# sonar_DAQ_old.net
KiCad netlist of a schematic drawn in Altium Designer
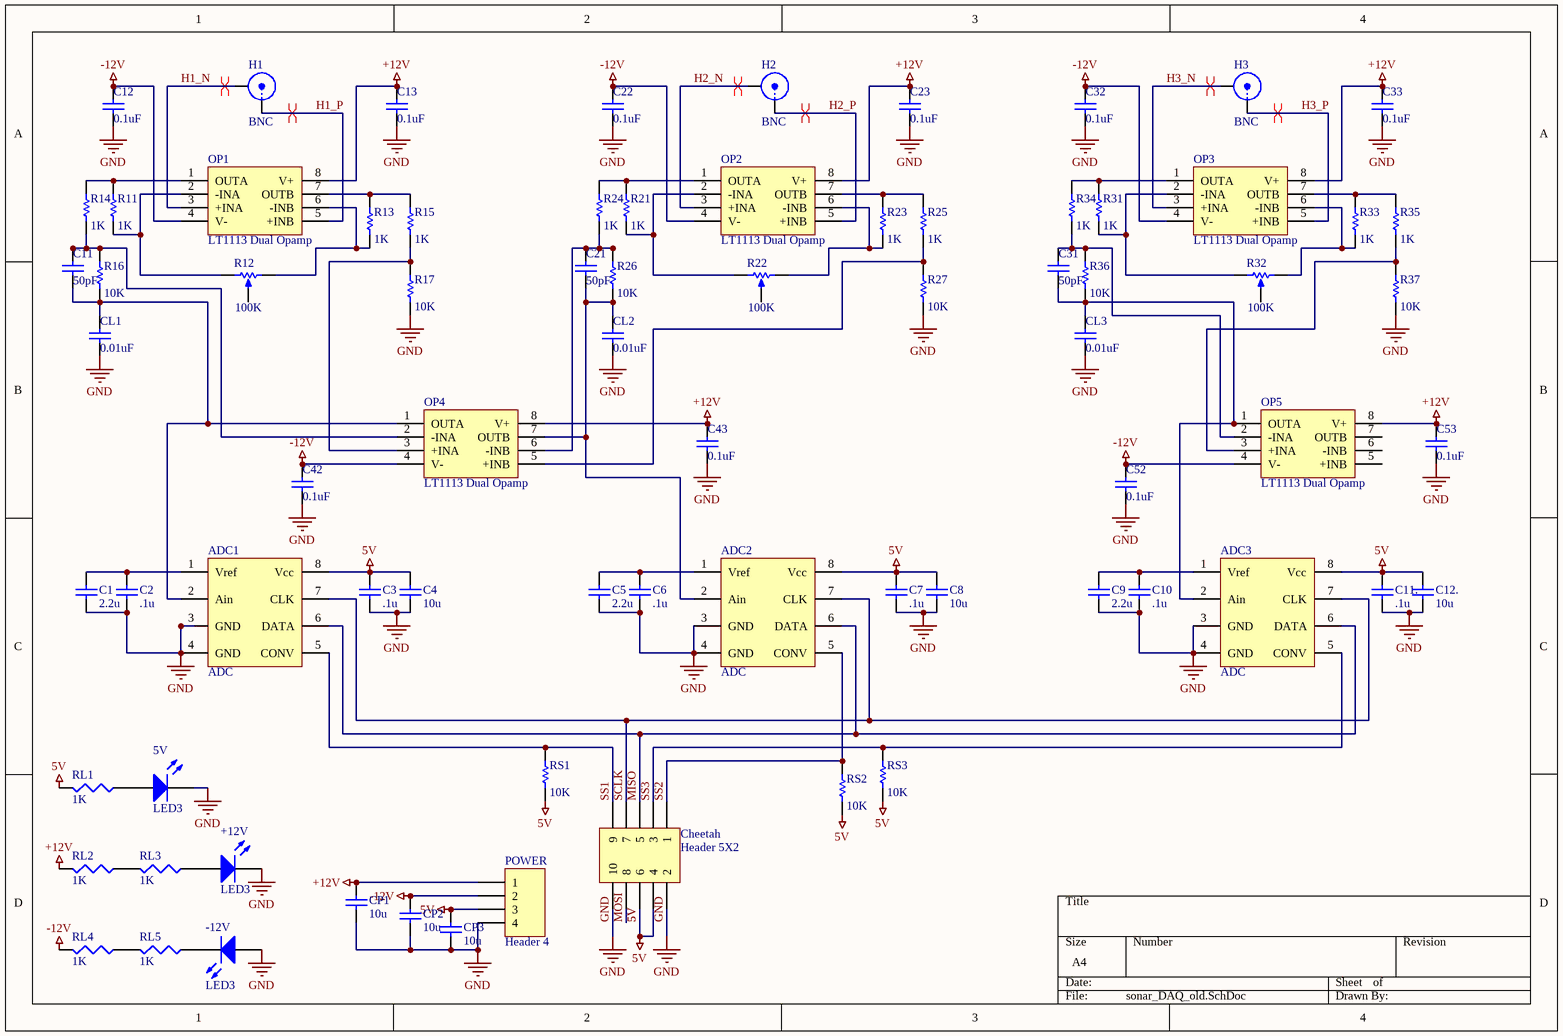
[diagram p0: sonar_DAQ_old.SchDoc]

(export (version "E")
  (design (tool "Eeschema 10.0.6"))
  (components
    (comp (ref "+12V")
      (value "LED3")
      (footprint "0805_led")
      (description "Typical BLUE SiC LED")
      (fields (field (name "PUBLISHER") "Altium Limited"))
      (libsource (lib "Miscellaneous Devices") (part "LED3"))
    )
    (comp (ref "-12V")
      (value "LED3")
      (footprint "0805_led")
      (description "Typical BLUE SiC LED")
      (fields (field (name "PUBLISHER") "Altium Limited"))
      (libsource (lib "Miscellaneous Devices") (part "LED3"))
    )
    (comp (ref "5V")
      (value "LED3")
      (footprint "0805_led")
      (description "Typical BLUE SiC LED")
      (fields (field (name "PUBLISHER") "Altium Limited"))
      (libsource (lib "Miscellaneous Devices") (part "LED3"))
    )
    (comp (ref "ADC1")
      (value "ADC")
      (footprint "ADC")
      (description "ADS7835")
      (libsource (lib "sonar_DAQ") (part "ADC"))
    )
    (comp (ref "ADC2")
      (value "ADC")
      (footprint "ADC")
      (description "ADS7835")
      (libsource (lib "sonar_DAQ") (part "ADC"))
    )
    (comp (ref "ADC3")
      (value "ADC")
      (footprint "ADC")
      (description "ADS7835")
      (libsource (lib "sonar_DAQ") (part "ADC"))
    )
    (comp (ref "C1")
      (value "2.2u")
      (footprint "0805_tantalum_cap")
      (description "Capacitor")
      (fields (field (name "PUBLISHER") "Altium Limited"))
      (libsource (lib "Miscellaneous Devices") (part "Cap"))
    )
    (comp (ref "C2")
      (value ".1u")
      (footprint "0805_ceramic_cap")
      (description "Capacitor")
      (fields (field (name "PUBLISHER") "Altium Limited"))
      (libsource (lib "Miscellaneous Devices") (part "Cap"))
    )
    (comp (ref "C3")
      (value ".1u")
      (footprint "0805_ceramic_cap")
      (description "Capacitor")
      (fields (field (name "PUBLISHER") "Altium Limited"))
      (libsource (lib "Miscellaneous Devices") (part "Cap"))
    )
    (comp (ref "C4")
      (value "10u")
      (footprint "0805_tantalum_cap")
      (description "Capacitor")
      (fields (field (name "PUBLISHER") "Altium Limited"))
      (libsource (lib "Miscellaneous Devices") (part "Cap"))
    )
    (comp (ref "C5")
      (value "2.2u")
      (footprint "0805_tantalum_cap")
      (description "Capacitor")
      (fields (field (name "PUBLISHER") "Altium Limited"))
      (libsource (lib "Miscellaneous Devices") (part "Cap"))
    )
    (comp (ref "C6")
      (value ".1u")
      (footprint "0805_ceramic_cap")
      (description "Capacitor")
      (fields (field (name "PUBLISHER") "Altium Limited"))
      (libsource (lib "Miscellaneous Devices") (part "Cap"))
    )
    (comp (ref "C7")
      (value ".1u")
      (footprint "0805_ceramic_cap")
      (description "Capacitor")
      (fields (field (name "PUBLISHER") "Altium Limited"))
      (libsource (lib "Miscellaneous Devices") (part "Cap"))
    )
    (comp (ref "C8")
      (value "10u")
      (footprint "0805_tantalum_cap")
      (description "Capacitor")
      (fields (field (name "PUBLISHER") "Altium Limited"))
      (libsource (lib "Miscellaneous Devices") (part "Cap"))
    )
    (comp (ref "C9")
      (value "2.2u")
      (footprint "0805_tantalum_cap")
      (description "Capacitor")
      (fields (field (name "PUBLISHER") "Altium Limited"))
      (libsource (lib "Miscellaneous Devices") (part "Cap"))
    )
    (comp (ref "C10")
      (value ".1u")
      (footprint "0805_ceramic_cap")
      (description "Capacitor")
      (fields (field (name "PUBLISHER") "Altium Limited"))
      (libsource (lib "Miscellaneous Devices") (part "Cap"))
    )
    (comp (ref "C11")
      (value "50pF")
      (footprint "0805_ceramic_cap")
      (description "Capacitor")
      (fields (field (name "Comment") "Cap") (field (name "PUBLISHER") "Altium Limited"))
      (libsource (lib "Miscellaneous Devices") (part "Cap"))
    )
    (comp (ref "C11.")
      (value ".1u")
      (footprint "0805_ceramic_cap")
      (description "Capacitor")
      (fields (field (name "PUBLISHER") "Altium Limited"))
      (libsource (lib "Miscellaneous Devices") (part "Cap"))
    )
    (comp (ref "C12")
      (value "0.1uF")
      (footprint "0805_ceramic_cap")
      (description "Capacitor")
      (fields (field (name "Comment") "Cap") (field (name "PUBLISHER") "Altium Limited"))
      (libsource (lib "Miscellaneous Devices") (part "Cap"))
    )
    (comp (ref "C12.")
      (value "10u")
      (footprint "0805_tantalum_cap")
      (description "Capacitor")
      (fields (field (name "PUBLISHER") "Altium Limited"))
      (libsource (lib "Miscellaneous Devices") (part "Cap"))
    )
    (comp (ref "C13")
      (value "0.1uF")
      (footprint "0805_ceramic_cap")
      (description "Capacitor")
      (fields (field (name "Comment") "Cap") (field (name "PUBLISHER") "Altium Limited"))
      (libsource (lib "Miscellaneous Devices") (part "Cap"))
    )
    (comp (ref "C21")
      (value "50pF")
      (footprint "0805_ceramic_cap")
      (description "Capacitor")
      (fields (field (name "Comment") "Cap") (field (name "PUBLISHER") "Altium Limited"))
      (libsource (lib "Miscellaneous Devices") (part "Cap"))
    )
    (comp (ref "C22")
      (value "0.1uF")
      (footprint "0805_ceramic_cap")
      (description "Capacitor")
      (fields (field (name "Comment") "Cap") (field (name "PUBLISHER") "Altium Limited"))
      (libsource (lib "Miscellaneous Devices") (part "Cap"))
    )
    (comp (ref "C23")
      (value "0.1uF")
      (footprint "0805_ceramic_cap")
      (description "Capacitor")
      (fields (field (name "Comment") "Cap") (field (name "PUBLISHER") "Altium Limited"))
      (libsource (lib "Miscellaneous Devices") (part "Cap"))
    )
    (comp (ref "C31")
      (value "50pF")
      (footprint "0805_ceramic_cap")
      (description "Capacitor")
      (fields (field (name "Comment") "Cap") (field (name "PUBLISHER") "Altium Limited"))
      (libsource (lib "Miscellaneous Devices") (part "Cap"))
    )
    (comp (ref "C32")
      (value "0.1uF")
      (footprint "0805_ceramic_cap")
      (description "Capacitor")
      (fields (field (name "Comment") "Cap") (field (name "PUBLISHER") "Altium Limited"))
      (libsource (lib "Miscellaneous Devices") (part "Cap"))
    )
    (comp (ref "C33")
      (value "0.1uF")
      (footprint "0805_ceramic_cap")
      (description "Capacitor")
      (fields (field (name "Comment") "Cap") (field (name "PUBLISHER") "Altium Limited"))
      (libsource (lib "Miscellaneous Devices") (part "Cap"))
    )
    (comp (ref "C42")
      (value "0.1uF")
      (footprint "0805_ceramic_cap")
      (description "Capacitor")
      (fields (field (name "Comment") "Cap") (field (name "PUBLISHER") "Altium Limited"))
      (libsource (lib "Miscellaneous Devices") (part "Cap"))
    )
    (comp (ref "C43")
      (value "0.1uF")
      (footprint "0805_ceramic_cap")
      (description "Capacitor")
      (fields (field (name "Comment") "Cap") (field (name "PUBLISHER") "Altium Limited"))
      (libsource (lib "Miscellaneous Devices") (part "Cap"))
    )
    (comp (ref "C52")
      (value "0.1uF")
      (footprint "0805_ceramic_cap")
      (description "Capacitor")
      (fields (field (name "Comment") "Cap") (field (name "PUBLISHER") "Altium Limited"))
      (libsource (lib "Miscellaneous Devices") (part "Cap"))
    )
    (comp (ref "C53")
      (value "0.1uF")
      (footprint "0805_ceramic_cap")
      (description "Capacitor")
      (fields (field (name "Comment") "Cap") (field (name "PUBLISHER") "Altium Limited"))
      (libsource (lib "Miscellaneous Devices") (part "Cap"))
    )
    (comp (ref "Cheetah")
      (value "Header 5X2")
      (footprint "HDR2X5")
      (description "Header, 5-Pin, Dual row")
      (fields (field (name "PUBLISHER") "Altium Limited"))
      (libsource (lib "Miscellaneous Connectors") (part "Header 5X2"))
    )
    (comp (ref "CL1")
      (value "0.01uF")
      (footprint "0805_ceramic_cap")
      (description "Capacitor")
      (fields (field (name "Comment") "Cap") (field (name "PUBLISHER") "Altium Limited"))
      (libsource (lib "Miscellaneous Devices") (part "Cap"))
    )
    (comp (ref "CL2")
      (value "0.01uF")
      (footprint "0805_ceramic_cap")
      (description "Capacitor")
      (fields (field (name "Comment") "Cap") (field (name "PUBLISHER") "Altium Limited"))
      (libsource (lib "Miscellaneous Devices") (part "Cap"))
    )
    (comp (ref "CL3")
      (value "0.01uF")
      (footprint "0805_ceramic_cap")
      (description "Capacitor")
      (fields (field (name "Comment") "Cap") (field (name "PUBLISHER") "Altium Limited"))
      (libsource (lib "Miscellaneous Devices") (part "Cap"))
    )
    (comp (ref "CP1")
      (value "10u")
      (footprint "0805_tantalum_cap")
      (description "Capacitor")
      (fields (field (name "PUBLISHER") "Altium Limited"))
      (libsource (lib "Miscellaneous Devices") (part "Cap"))
    )
    (comp (ref "CP2")
      (value "10u")
      (footprint "0805_tantalum_cap")
      (description "Capacitor")
      (fields (field (name "PUBLISHER") "Altium Limited"))
      (libsource (lib "Miscellaneous Devices") (part "Cap"))
    )
    (comp (ref "CP3")
      (value "10u")
      (footprint "0805_tantalum_cap")
      (description "Capacitor")
      (fields (field (name "PUBLISHER") "Altium Limited"))
      (libsource (lib "Miscellaneous Devices") (part "Cap"))
    )
    (comp (ref "H1")
      (value "BNC")
      (footprint "BNC")
      (description "BNC Elbow Connector")
      (fields (field (name "PUBLISHER") "Altium Limited"))
      (libsource (lib "Miscellaneous Connectors") (part "BNC"))
    )
    (comp (ref "H2")
      (value "BNC")
      (footprint "BNC")
      (description "BNC Elbow Connector")
      (fields (field (name "PUBLISHER") "Altium Limited"))
      (libsource (lib "Miscellaneous Connectors") (part "BNC"))
    )
    (comp (ref "H3")
      (value "BNC")
      (footprint "BNC")
      (description "BNC Elbow Connector")
      (fields (field (name "PUBLISHER") "Altium Limited"))
      (libsource (lib "Miscellaneous Connectors") (part "BNC"))
    )
    (comp (ref "OP1")
      (value "LT1113 Dual Opamp")
      (footprint "lt1113_opamp")
      (libsource (lib "sonar_DAQ") (part "LT1113 OPAMP"))
    )
    (comp (ref "OP2")
      (value "LT1113 Dual Opamp")
      (footprint "lt1113_opamp")
      (libsource (lib "sonar_DAQ") (part "LT1113 OPAMP"))
    )
    (comp (ref "OP3")
      (value "LT1113 Dual Opamp")
      (footprint "lt1113_opamp")
      (libsource (lib "sonar_DAQ") (part "LT1113 OPAMP"))
    )
    (comp (ref "OP4")
      (value "LT1113 Dual Opamp")
      (footprint "lt1113_opamp")
      (libsource (lib "sonar_DAQ") (part "LT1113 OPAMP"))
    )
    (comp (ref "OP5")
      (value "LT1113 Dual Opamp")
      (footprint "lt1113_opamp")
      (libsource (lib "sonar_DAQ") (part "LT1113 OPAMP"))
    )
    (comp (ref "POWER")
      (value "Header 4")
      (footprint "HDR1X4")
      (description "Header, 4-Pin")
      (fields (field (name "PUBLISHER") "Altium Limited"))
      (libsource (lib "Miscellaneous Connectors") (part "Header 4"))
    )
    (comp (ref "R11")
      (value "1K")
      (footprint "0805_res")
      (description "Resistor")
      (fields (field (name "Comment") "Res1") (field (name "PUBLISHER") "Altium Limited"))
      (libsource (lib "Miscellaneous Devices") (part "Res1"))
    )
    (comp (ref "R12")
      (value "100K")
      (footprint "trimmer_pot")
      (description "Potentiometer")
      (fields (field (name "Comment") "RPot") (field (name "PUBLISHER") "Altium Limited"))
      (libsource (lib "Miscellaneous Devices") (part "RPot"))
    )
    (comp (ref "R13")
      (value "1K")
      (footprint "0805_res")
      (description "Resistor")
      (fields (field (name "Comment") "Res1") (field (name "PUBLISHER") "Altium Limited"))
      (libsource (lib "Miscellaneous Devices") (part "Res1"))
    )
    (comp (ref "R14")
      (value "1K")
      (footprint "0805_res")
      (description "Resistor")
      (fields (field (name "Comment") "Res1") (field (name "PUBLISHER") "Altium Limited"))
      (libsource (lib "Miscellaneous Devices") (part "Res1"))
    )
    (comp (ref "R15")
      (value "1K")
      (footprint "0805_res")
      (description "Resistor")
      (fields (field (name "Comment") "Res1") (field (name "PUBLISHER") "Altium Limited"))
      (libsource (lib "Miscellaneous Devices") (part "Res1"))
    )
    (comp (ref "R16")
      (value "10K")
      (footprint "0805_res")
      (description "Resistor")
      (fields (field (name "Comment") "Res1") (field (name "PUBLISHER") "Altium Limited"))
      (libsource (lib "Miscellaneous Devices") (part "Res1"))
    )
    (comp (ref "R17")
      (value "10K")
      (footprint "0805_res")
      (description "Resistor")
      (fields (field (name "Comment") "Res1") (field (name "PUBLISHER") "Altium Limited"))
      (libsource (lib "Miscellaneous Devices") (part "Res1"))
    )
    (comp (ref "R21")
      (value "1K")
      (footprint "0805_res")
      (description "Resistor")
      (fields (field (name "Comment") "Res1") (field (name "PUBLISHER") "Altium Limited"))
      (libsource (lib "Miscellaneous Devices") (part "Res1"))
    )
    (comp (ref "R22")
      (value "100K")
      (footprint "trimmer_pot")
      (description "Potentiometer")
      (fields (field (name "Comment") "RPot") (field (name "PUBLISHER") "Altium Limited"))
      (libsource (lib "Miscellaneous Devices") (part "RPot"))
    )
    (comp (ref "R23")
      (value "1K")
      (footprint "0805_res")
      (description "Resistor")
      (fields (field (name "Comment") "Res1") (field (name "PUBLISHER") "Altium Limited"))
      (libsource (lib "Miscellaneous Devices") (part "Res1"))
    )
    (comp (ref "R24")
      (value "1K")
      (footprint "0805_res")
      (description "Resistor")
      (fields (field (name "Comment") "Res1") (field (name "PUBLISHER") "Altium Limited"))
      (libsource (lib "Miscellaneous Devices") (part "Res1"))
    )
    (comp (ref "R25")
      (value "1K")
      (footprint "0805_res")
      (description "Resistor")
      (fields (field (name "Comment") "Res1") (field (name "PUBLISHER") "Altium Limited"))
      (libsource (lib "Miscellaneous Devices") (part "Res1"))
    )
    (comp (ref "R26")
      (value "10K")
      (footprint "0805_res")
      (description "Resistor")
      (fields (field (name "Comment") "Res1") (field (name "PUBLISHER") "Altium Limited"))
      (libsource (lib "Miscellaneous Devices") (part "Res1"))
    )
    (comp (ref "R27")
      (value "10K")
      (footprint "0805_res")
      (description "Resistor")
      (fields (field (name "Comment") "Res1") (field (name "PUBLISHER") "Altium Limited"))
      (libsource (lib "Miscellaneous Devices") (part "Res1"))
    )
    (comp (ref "R31")
      (value "1K")
      (footprint "0805_res")
      (description "Resistor")
      (fields (field (name "Comment") "Res1") (field (name "PUBLISHER") "Altium Limited"))
      (libsource (lib "Miscellaneous Devices") (part "Res1"))
    )
    (comp (ref "R32")
      (value "100K")
      (footprint "trimmer_pot")
      (description "Potentiometer")
      (fields (field (name "Comment") "RPot") (field (name "PUBLISHER") "Altium Limited"))
      (libsource (lib "Miscellaneous Devices") (part "RPot"))
    )
    (comp (ref "R33")
      (value "1K")
      (footprint "0805_res")
      (description "Resistor")
      (fields (field (name "Comment") "Res1") (field (name "PUBLISHER") "Altium Limited"))
      (libsource (lib "Miscellaneous Devices") (part "Res1"))
    )
    (comp (ref "R34")
      (value "1K")
      (footprint "0805_res")
      (description "Resistor")
      (fields (field (name "Comment") "Res1") (field (name "PUBLISHER") "Altium Limited"))
      (libsource (lib "Miscellaneous Devices") (part "Res1"))
    )
    (comp (ref "R35")
      (value "1K")
      (footprint "0805_res")
      (description "Resistor")
      (fields (field (name "Comment") "Res1") (field (name "PUBLISHER") "Altium Limited"))
      (libsource (lib "Miscellaneous Devices") (part "Res1"))
    )
    (comp (ref "R36")
      (value "10K")
      (footprint "0805_res")
      (description "Resistor")
      (fields (field (name "Comment") "Res1") (field (name "PUBLISHER") "Altium Limited"))
      (libsource (lib "Miscellaneous Devices") (part "Res1"))
    )
    (comp (ref "R37")
      (value "10K")
      (footprint "0805_res")
      (description "Resistor")
      (fields (field (name "Comment") "Res1") (field (name "PUBLISHER") "Altium Limited"))
      (libsource (lib "Miscellaneous Devices") (part "Res1"))
    )
    (comp (ref "RL1")
      (value "1K")
      (footprint "0805_res")
      (description "Resistor")
      (fields (field (name "Comment") "Res3") (field (name "PUBLISHER") "Altium Limited"))
      (libsource (lib "Miscellaneous Devices") (part "Res3"))
    )
    (comp (ref "RL2")
      (value "1K")
      (footprint "0805_res")
      (description "Resistor")
      (fields (field (name "Comment") "Res3") (field (name "PUBLISHER") "Altium Limited"))
      (libsource (lib "Miscellaneous Devices") (part "Res3"))
    )
    (comp (ref "RL3")
      (value "1K")
      (footprint "0805_res")
      (description "Resistor")
      (fields (field (name "Comment") "Res3") (field (name "PUBLISHER") "Altium Limited"))
      (libsource (lib "Miscellaneous Devices") (part "Res3"))
    )
    (comp (ref "RL4")
      (value "1K")
      (footprint "0805_res")
      (description "Resistor")
      (fields (field (name "Comment") "Res3") (field (name "PUBLISHER") "Altium Limited"))
      (libsource (lib "Miscellaneous Devices") (part "Res3"))
    )
    (comp (ref "RL5")
      (value "1K")
      (footprint "0805_res")
      (description "Resistor")
      (fields (field (name "Comment") "Res3") (field (name "PUBLISHER") "Altium Limited"))
      (libsource (lib "Miscellaneous Devices") (part "Res3"))
    )
    (comp (ref "RS1")
      (value "10K")
      (footprint "0805_res")
      (description "Resistor")
      (fields (field (name "Comment") "Res1") (field (name "PUBLISHER") "Altium Limited"))
      (libsource (lib "Miscellaneous Devices") (part "Res1"))
    )
    (comp (ref "RS2")
      (value "10K")
      (footprint "0805_res")
      (description "Resistor")
      (fields (field (name "Comment") "Res1") (field (name "PUBLISHER") "Altium Limited"))
      (libsource (lib "Miscellaneous Devices") (part "Res1"))
    )
    (comp (ref "RS3")
      (value "10K")
      (footprint "0805_res")
      (description "Resistor")
      (fields (field (name "Comment") "Res1") (field (name "PUBLISHER") "Altium Limited"))
      (libsource (lib "Miscellaneous Devices") (part "Res1"))
    )
  )
  (nets
    (net (code "1") (name "+12V") (class "Default")
      (node (ref "C13") (pin "2") (pinfunction "2_2") (pintype "passive"))
      (node (ref "C23") (pin "2") (pinfunction "2_2") (pintype "passive"))
      (node (ref "C33") (pin "2") (pinfunction "2_2") (pintype "passive"))
      (node (ref "C43") (pin "2") (pinfunction "2_2") (pintype "passive"))
      (node (ref "C53") (pin "2") (pinfunction "2_2") (pintype "passive"))
      (node (ref "CP1") (pin "1") (pinfunction "1_1") (pintype "passive"))
      (node (ref "OP1") (pin "8") (pinfunction "V+_8") (pintype "power_in"))
      (node (ref "OP2") (pin "8") (pinfunction "V+_8") (pintype "power_in"))
      (node (ref "OP3") (pin "8") (pinfunction "V+_8") (pintype "power_in"))
      (node (ref "OP4") (pin "8") (pinfunction "V+_8") (pintype "power_in"))
      (node (ref "OP5") (pin "8") (pinfunction "V+_8") (pintype "power_in"))
      (node (ref "POWER") (pin "1") (pinfunction "1_1") (pintype "passive"))
      (node (ref "RL2") (pin "2") (pinfunction "2_2") (pintype "passive"))
    )
    (net (code "2") (name "-12V") (class "Default")
      (node (ref "C12") (pin "2") (pinfunction "2_2") (pintype "passive"))
      (node (ref "C22") (pin "2") (pinfunction "2_2") (pintype "passive"))
      (node (ref "C32") (pin "2") (pinfunction "2_2") (pintype "passive"))
      (node (ref "C42") (pin "2") (pinfunction "2_2") (pintype "passive"))
      (node (ref "C52") (pin "2") (pinfunction "2_2") (pintype "passive"))
      (node (ref "CP2") (pin "1") (pinfunction "1_1") (pintype "passive"))
      (node (ref "OP1") (pin "4") (pinfunction "V-_4") (pintype "power_in"))
      (node (ref "OP2") (pin "4") (pinfunction "V-_4") (pintype "power_in"))
      (node (ref "OP3") (pin "4") (pinfunction "V-_4") (pintype "power_in"))
      (node (ref "OP4") (pin "4") (pinfunction "V-_4") (pintype "power_in"))
      (node (ref "OP5") (pin "4") (pinfunction "V-_4") (pintype "power_in"))
      (node (ref "POWER") (pin "2") (pinfunction "2_2") (pintype "passive"))
      (node (ref "RL4") (pin "2") (pinfunction "2_2") (pintype "passive"))
    )
    (net (code "3") (name "/H1_N") (class "Default")
      (node (ref "H1") (pin "2") (pinfunction "Y_2") (pintype "passive"))
      (node (ref "OP1") (pin "3") (pinfunction "+INA_3") (pintype "power_in"))
    )
    (net (code "4") (name "/H1_P") (class "Default")
      (node (ref "H1") (pin "1") (pinfunction "X_1") (pintype "passive"))
      (node (ref "OP1") (pin "5") (pinfunction "+INB_5") (pintype "power_in"))
    )
    (net (code "5") (name "/H2_N") (class "Default")
      (node (ref "H2") (pin "2") (pinfunction "Y_2") (pintype "passive"))
      (node (ref "OP2") (pin "3") (pinfunction "+INA_3") (pintype "power_in"))
    )
    (net (code "6") (name "/H2_P") (class "Default")
      (node (ref "H2") (pin "1") (pinfunction "X_1") (pintype "passive"))
      (node (ref "OP2") (pin "5") (pinfunction "+INB_5") (pintype "power_in"))
    )
    (net (code "7") (name "/H3_N") (class "Default")
      (node (ref "H3") (pin "2") (pinfunction "Y_2") (pintype "passive"))
      (node (ref "OP3") (pin "3") (pinfunction "+INA_3") (pintype "power_in"))
    )
    (net (code "8") (name "/H3_P") (class "Default")
      (node (ref "H3") (pin "1") (pinfunction "X_1") (pintype "passive"))
      (node (ref "OP3") (pin "5") (pinfunction "+INB_5") (pintype "power_in"))
    )
    (net (code "9") (name "/MISO") (class "Default")
      (node (ref "ADC1") (pin "6") (pinfunction "DATA_6") (pintype "power_in"))
      (node (ref "ADC2") (pin "6") (pinfunction "DATA_6") (pintype "power_in"))
      (node (ref "ADC3") (pin "6") (pinfunction "DATA_6") (pintype "power_in"))
      (node (ref "Cheetah") (pin "5") (pinfunction "5_5") (pintype "passive"))
    )
    (net (code "10") (name "/MOSI") (class "Default")
      (node (ref "Cheetah") (pin "8") (pinfunction "8_8") (pintype "passive"))
    )
    (net (code "11") (name "/SCLK") (class "Default")
      (node (ref "ADC1") (pin "7") (pinfunction "CLK_7") (pintype "power_in"))
      (node (ref "ADC2") (pin "7") (pinfunction "CLK_7") (pintype "power_in"))
      (node (ref "ADC3") (pin "7") (pinfunction "CLK_7") (pintype "power_in"))
      (node (ref "Cheetah") (pin "7") (pinfunction "7_7") (pintype "passive"))
    )
    (net (code "12") (name "/SS1") (class "Default")
      (node (ref "ADC1") (pin "5") (pinfunction "CONV_5") (pintype "power_in"))
      (node (ref "Cheetah") (pin "9") (pinfunction "9_9") (pintype "passive"))
      (node (ref "RS1") (pin "2") (pinfunction "2_2") (pintype "passive"))
    )
    (net (code "13") (name "/SS2") (class "Default")
      (node (ref "ADC2") (pin "5") (pinfunction "CONV_5") (pintype "power_in"))
      (node (ref "Cheetah") (pin "1") (pinfunction "1_1") (pintype "passive"))
      (node (ref "RS2") (pin "2") (pinfunction "2_2") (pintype "passive"))
    )
    (net (code "14") (name "/SS3") (class "Default")
      (node (ref "ADC3") (pin "5") (pinfunction "CONV_5") (pintype "power_in"))
      (node (ref "Cheetah") (pin "3") (pinfunction "3_3") (pintype "passive"))
      (node (ref "RS3") (pin "2") (pinfunction "2_2") (pintype "passive"))
    )
    (net (code "15") (name "5V") (class "Default")
      (node (ref "ADC1") (pin "8") (pinfunction "Vcc_8") (pintype "power_in"))
      (node (ref "ADC2") (pin "8") (pinfunction "Vcc_8") (pintype "power_in"))
      (node (ref "ADC3") (pin "8") (pinfunction "Vcc_8") (pintype "power_in"))
      (node (ref "C11.") (pin "1") (pinfunction "1_1") (pintype "passive"))
      (node (ref "C12.") (pin "1") (pinfunction "1_1") (pintype "passive"))
      (node (ref "C3") (pin "1") (pinfunction "1_1") (pintype "passive"))
      (node (ref "C4") (pin "1") (pinfunction "1_1") (pintype "passive"))
      (node (ref "C7") (pin "1") (pinfunction "1_1") (pintype "passive"))
      (node (ref "C8") (pin "1") (pinfunction "1_1") (pintype "passive"))
      (node (ref "CP3") (pin "1") (pinfunction "1_1") (pintype "passive"))
      (node (ref "Cheetah") (pin "4") (pinfunction "4_4") (pintype "passive"))
      (node (ref "Cheetah") (pin "6") (pinfunction "6_6") (pintype "passive"))
      (node (ref "POWER") (pin "3") (pinfunction "3_3") (pintype "passive"))
      (node (ref "RL1") (pin "2") (pinfunction "2_2") (pintype "passive"))
      (node (ref "RS1") (pin "1") (pinfunction "1_1") (pintype "passive"))
      (node (ref "RS2") (pin "1") (pinfunction "1_1") (pintype "passive"))
      (node (ref "RS3") (pin "1") (pinfunction "1_1") (pintype "passive"))
    )
    (net (code "16") (name "GND") (class "Default")
      (node (ref "+12V") (pin "2") (pinfunction "K_2") (pintype "passive"))
      (node (ref "-12V") (pin "1") (pinfunction "A_1") (pintype "passive"))
      (node (ref "5V") (pin "2") (pinfunction "K_2") (pintype "passive"))
      (node (ref "ADC1") (pin "3") (pinfunction "GND_3") (pintype "power_in"))
      (node (ref "ADC1") (pin "4") (pinfunction "GND_4") (pintype "power_in"))
      (node (ref "ADC2") (pin "3") (pinfunction "GND_3") (pintype "power_in"))
      (node (ref "ADC2") (pin "4") (pinfunction "GND_4") (pintype "power_in"))
      (node (ref "ADC3") (pin "3") (pinfunction "GND_3") (pintype "power_in"))
      (node (ref "ADC3") (pin "4") (pinfunction "GND_4") (pintype "power_in"))
      (node (ref "C1") (pin "2") (pinfunction "2_2") (pintype "passive"))
      (node (ref "C10") (pin "2") (pinfunction "2_2") (pintype "passive"))
      (node (ref "C11.") (pin "2") (pinfunction "2_2") (pintype "passive"))
      (node (ref "C12") (pin "1") (pinfunction "1_1") (pintype "passive"))
      (node (ref "C12.") (pin "2") (pinfunction "2_2") (pintype "passive"))
      (node (ref "C13") (pin "1") (pinfunction "1_1") (pintype "passive"))
      (node (ref "C2") (pin "2") (pinfunction "2_2") (pintype "passive"))
      (node (ref "C22") (pin "1") (pinfunction "1_1") (pintype "passive"))
      (node (ref "C23") (pin "1") (pinfunction "1_1") (pintype "passive"))
      (node (ref "C3") (pin "2") (pinfunction "2_2") (pintype "passive"))
      (node (ref "C32") (pin "1") (pinfunction "1_1") (pintype "passive"))
      (node (ref "C33") (pin "1") (pinfunction "1_1") (pintype "passive"))
      (node (ref "C4") (pin "2") (pinfunction "2_2") (pintype "passive"))
      (node (ref "C42") (pin "1") (pinfunction "1_1") (pintype "passive"))
      (node (ref "C43") (pin "1") (pinfunction "1_1") (pintype "passive"))
      (node (ref "C5") (pin "2") (pinfunction "2_2") (pintype "passive"))
      (node (ref "C52") (pin "1") (pinfunction "1_1") (pintype "passive"))
      (node (ref "C53") (pin "1") (pinfunction "1_1") (pintype "passive"))
      (node (ref "C6") (pin "2") (pinfunction "2_2") (pintype "passive"))
      (node (ref "C7") (pin "2") (pinfunction "2_2") (pintype "passive"))
      (node (ref "C8") (pin "2") (pinfunction "2_2") (pintype "passive"))
      (node (ref "C9") (pin "2") (pinfunction "2_2") (pintype "passive"))
      (node (ref "CL1") (pin "2") (pinfunction "2_2") (pintype "passive"))
      (node (ref "CL2") (pin "2") (pinfunction "2_2") (pintype "passive"))
      (node (ref "CL3") (pin "2") (pinfunction "2_2") (pintype "passive"))
      (node (ref "CP1") (pin "2") (pinfunction "2_2") (pintype "passive"))
      (node (ref "CP2") (pin "2") (pinfunction "2_2") (pintype "passive"))
      (node (ref "CP3") (pin "2") (pinfunction "2_2") (pintype "passive"))
      (node (ref "Cheetah") (pin "10") (pinfunction "10_10") (pintype "passive"))
      (node (ref "Cheetah") (pin "2") (pinfunction "2_2") (pintype "passive"))
      (node (ref "POWER") (pin "4") (pinfunction "4_4") (pintype "passive"))
      (node (ref "R17") (pin "1") (pinfunction "1_1") (pintype "passive"))
      (node (ref "R27") (pin "1") (pinfunction "1_1") (pintype "passive"))
      (node (ref "R37") (pin "1") (pinfunction "1_1") (pintype "passive"))
    )
    (net (code "17") (name "Net-(+12V-A)") (class "Default")
      (node (ref "+12V") (pin "1") (pinfunction "A_1") (pintype "passive"))
      (node (ref "RL3") (pin "1") (pinfunction "1_1") (pintype "passive"))
    )
    (net (code "18") (name "Net-(-12V-K)") (class "Default")
      (node (ref "-12V") (pin "2") (pinfunction "K_2") (pintype "passive"))
      (node (ref "RL5") (pin "1") (pinfunction "1_1") (pintype "passive"))
    )
    (net (code "19") (name "Net-(5V-A)") (class "Default")
      (node (ref "5V") (pin "1") (pinfunction "A_1") (pintype "passive"))
      (node (ref "RL1") (pin "1") (pinfunction "1_1") (pintype "passive"))
    )
    (net (code "20") (name "Net-(ADC1-Ain)") (class "Default")
      (node (ref "ADC1") (pin "2") (pinfunction "Ain_2") (pintype "power_in"))
      (node (ref "C11") (pin "1") (pinfunction "1_1") (pintype "passive"))
      (node (ref "CL1") (pin "1") (pinfunction "1_1") (pintype "passive"))
      (node (ref "OP4") (pin "1") (pinfunction "OUTA_1") (pintype "power_in"))
      (node (ref "R16") (pin "1") (pinfunction "1_1") (pintype "passive"))
    )
    (net (code "21") (name "Net-(ADC1-Vref)") (class "Default")
      (node (ref "ADC1") (pin "1") (pinfunction "Vref_1") (pintype "power_in"))
      (node (ref "C1") (pin "1") (pinfunction "1_1") (pintype "passive"))
      (node (ref "C2") (pin "1") (pinfunction "1_1") (pintype "passive"))
    )
    (net (code "22") (name "Net-(ADC2-Ain)") (class "Default")
      (node (ref "ADC2") (pin "2") (pinfunction "Ain_2") (pintype "power_in"))
      (node (ref "C21") (pin "1") (pinfunction "1_1") (pintype "passive"))
      (node (ref "CL2") (pin "1") (pinfunction "1_1") (pintype "passive"))
      (node (ref "OP4") (pin "7") (pinfunction "OUTB_7") (pintype "power_in"))
      (node (ref "R26") (pin "1") (pinfunction "1_1") (pintype "passive"))
    )
    (net (code "23") (name "Net-(ADC2-Vref)") (class "Default")
      (node (ref "ADC2") (pin "1") (pinfunction "Vref_1") (pintype "power_in"))
      (node (ref "C5") (pin "1") (pinfunction "1_1") (pintype "passive"))
      (node (ref "C6") (pin "1") (pinfunction "1_1") (pintype "passive"))
    )
    (net (code "24") (name "Net-(ADC3-Ain)") (class "Default")
      (node (ref "ADC3") (pin "2") (pinfunction "Ain_2") (pintype "power_in"))
      (node (ref "C31") (pin "1") (pinfunction "1_1") (pintype "passive"))
      (node (ref "CL3") (pin "1") (pinfunction "1_1") (pintype "passive"))
      (node (ref "OP5") (pin "1") (pinfunction "OUTA_1") (pintype "power_in"))
      (node (ref "R36") (pin "1") (pinfunction "1_1") (pintype "passive"))
    )
    (net (code "25") (name "Net-(ADC3-Vref)") (class "Default")
      (node (ref "ADC3") (pin "1") (pinfunction "Vref_1") (pintype "power_in"))
      (node (ref "C10") (pin "1") (pinfunction "1_1") (pintype "passive"))
      (node (ref "C9") (pin "1") (pinfunction "1_1") (pintype "passive"))
    )
    (net (code "26") (name "Net-(OP1--INA)") (class "Default")
      (node (ref "OP1") (pin "2") (pinfunction "-INA_2") (pintype "power_in"))
      (node (ref "R11") (pin "1") (pinfunction "1_1") (pintype "passive"))
      (node (ref "R12") (pin "1") (pinfunction "TOP_1") (pintype "passive"))
    )
    (net (code "27") (name "Net-(OP1--INB)") (class "Default")
      (node (ref "OP1") (pin "6") (pinfunction "-INB_6") (pintype "power_in"))
      (node (ref "R12") (pin "2") (pinfunction "BOT_2") (pintype "passive"))
      (node (ref "R13") (pin "1") (pinfunction "1_1") (pintype "passive"))
    )
    (net (code "28") (name "Net-(OP1-OUTA)") (class "Default")
      (node (ref "OP1") (pin "1") (pinfunction "OUTA_1") (pintype "power_in"))
      (node (ref "R11") (pin "2") (pinfunction "2_2") (pintype "passive"))
      (node (ref "R14") (pin "2") (pinfunction "2_2") (pintype "passive"))
    )
    (net (code "29") (name "Net-(OP1-OUTB)") (class "Default")
      (node (ref "OP1") (pin "7") (pinfunction "OUTB_7") (pintype "power_in"))
      (node (ref "R13") (pin "2") (pinfunction "2_2") (pintype "passive"))
      (node (ref "R15") (pin "2") (pinfunction "2_2") (pintype "passive"))
    )
    (net (code "30") (name "Net-(OP2--INA)") (class "Default")
      (node (ref "OP2") (pin "2") (pinfunction "-INA_2") (pintype "power_in"))
      (node (ref "R21") (pin "1") (pinfunction "1_1") (pintype "passive"))
      (node (ref "R22") (pin "1") (pinfunction "TOP_1") (pintype "passive"))
    )
    (net (code "31") (name "Net-(OP2--INB)") (class "Default")
      (node (ref "OP2") (pin "6") (pinfunction "-INB_6") (pintype "power_in"))
      (node (ref "R22") (pin "2") (pinfunction "BOT_2") (pintype "passive"))
      (node (ref "R23") (pin "1") (pinfunction "1_1") (pintype "passive"))
    )
    (net (code "32") (name "Net-(OP2-OUTA)") (class "Default")
      (node (ref "OP2") (pin "1") (pinfunction "OUTA_1") (pintype "power_in"))
      (node (ref "R21") (pin "2") (pinfunction "2_2") (pintype "passive"))
      (node (ref "R24") (pin "2") (pinfunction "2_2") (pintype "passive"))
    )
    (net (code "33") (name "Net-(OP2-OUTB)") (class "Default")
      (node (ref "OP2") (pin "7") (pinfunction "OUTB_7") (pintype "power_in"))
      (node (ref "R23") (pin "2") (pinfunction "2_2") (pintype "passive"))
      (node (ref "R25") (pin "2") (pinfunction "2_2") (pintype "passive"))
    )
    (net (code "34") (name "Net-(OP3--INA)") (class "Default")
      (node (ref "OP3") (pin "2") (pinfunction "-INA_2") (pintype "power_in"))
      (node (ref "R31") (pin "1") (pinfunction "1_1") (pintype "passive"))
      (node (ref "R32") (pin "1") (pinfunction "TOP_1") (pintype "passive"))
    )
    (net (code "35") (name "Net-(OP3--INB)") (class "Default")
      (node (ref "OP3") (pin "6") (pinfunction "-INB_6") (pintype "power_in"))
      (node (ref "R32") (pin "2") (pinfunction "BOT_2") (pintype "passive"))
      (node (ref "R33") (pin "1") (pinfunction "1_1") (pintype "passive"))
    )
    (net (code "36") (name "Net-(OP3-OUTA)") (class "Default")
      (node (ref "OP3") (pin "1") (pinfunction "OUTA_1") (pintype "power_in"))
      (node (ref "R31") (pin "2") (pinfunction "2_2") (pintype "passive"))
      (node (ref "R34") (pin "2") (pinfunction "2_2") (pintype "passive"))
    )
    (net (code "37") (name "Net-(OP3-OUTB)") (class "Default")
      (node (ref "OP3") (pin "7") (pinfunction "OUTB_7") (pintype "power_in"))
      (node (ref "R33") (pin "2") (pinfunction "2_2") (pintype "passive"))
      (node (ref "R35") (pin "2") (pinfunction "2_2") (pintype "passive"))
    )
    (net (code "38") (name "Net-(OP4-+INA)") (class "Default")
      (node (ref "OP4") (pin "3") (pinfunction "+INA_3") (pintype "power_in"))
      (node (ref "R15") (pin "1") (pinfunction "1_1") (pintype "passive"))
      (node (ref "R17") (pin "2") (pinfunction "2_2") (pintype "passive"))
    )
    (net (code "39") (name "Net-(OP4-+INB)") (class "Default")
      (node (ref "OP4") (pin "5") (pinfunction "+INB_5") (pintype "power_in"))
      (node (ref "R25") (pin "1") (pinfunction "1_1") (pintype "passive"))
      (node (ref "R27") (pin "2") (pinfunction "2_2") (pintype "passive"))
    )
    (net (code "40") (name "Net-(OP4--INA)") (class "Default")
      (node (ref "C11") (pin "2") (pinfunction "2_2") (pintype "passive"))
      (node (ref "OP4") (pin "2") (pinfunction "-INA_2") (pintype "power_in"))
      (node (ref "R14") (pin "1") (pinfunction "1_1") (pintype "passive"))
      (node (ref "R16") (pin "2") (pinfunction "2_2") (pintype "passive"))
    )
    (net (code "41") (name "Net-(OP4--INB)") (class "Default")
      (node (ref "C21") (pin "2") (pinfunction "2_2") (pintype "passive"))
      (node (ref "OP4") (pin "6") (pinfunction "-INB_6") (pintype "power_in"))
      (node (ref "R24") (pin "1") (pinfunction "1_1") (pintype "passive"))
      (node (ref "R26") (pin "2") (pinfunction "2_2") (pintype "passive"))
    )
    (net (code "42") (name "Net-(OP5-+INA)") (class "Default")
      (node (ref "OP5") (pin "3") (pinfunction "+INA_3") (pintype "power_in"))
      (node (ref "R35") (pin "1") (pinfunction "1_1") (pintype "passive"))
      (node (ref "R37") (pin "2") (pinfunction "2_2") (pintype "passive"))
    )
    (net (code "43") (name "Net-(OP5--INA)") (class "Default")
      (node (ref "C31") (pin "2") (pinfunction "2_2") (pintype "passive"))
      (node (ref "OP5") (pin "2") (pinfunction "-INA_2") (pintype "power_in"))
      (node (ref "R34") (pin "1") (pinfunction "1_1") (pintype "passive"))
      (node (ref "R36") (pin "2") (pinfunction "2_2") (pintype "passive"))
    )
    (net (code "44") (name "Net-(RL2-Pad1)") (class "Default")
      (node (ref "RL2") (pin "1") (pinfunction "1_1") (pintype "passive"))
      (node (ref "RL3") (pin "2") (pinfunction "2_2") (pintype "passive"))
    )
    (net (code "45") (name "Net-(RL4-Pad1)") (class "Default")
      (node (ref "RL4") (pin "1") (pinfunction "1_1") (pintype "passive"))
      (node (ref "RL5") (pin "2") (pinfunction "2_2") (pintype "passive"))
    )
    (net (code "46") (name "unconnected-(OP5-+INB-Pad5)") (class "Default")
      (node (ref "OP5") (pin "5") (pinfunction "+INB_5") (pintype "power_in"))
    )
    (net (code "47") (name "unconnected-(OP5--INB-Pad6)") (class "Default")
      (node (ref "OP5") (pin "6") (pinfunction "-INB_6") (pintype "power_in"))
    )
    (net (code "48") (name "unconnected-(OP5-OUTB-Pad7)") (class "Default")
      (node (ref "OP5") (pin "7") (pinfunction "OUTB_7") (pintype "power_in"))
    )
    (net (code "49") (name "unconnected-(R12-TAP-Pad3)") (class "Default")
      (node (ref "R12") (pin "3") (pinfunction "TAP_3") (pintype "passive"))
    )
    (net (code "50") (name "unconnected-(R22-TAP-Pad3)") (class "Default")
      (node (ref "R22") (pin "3") (pinfunction "TAP_3") (pintype "passive"))
    )
    (net (code "51") (name "unconnected-(R32-TAP-Pad3)") (class "Default")
      (node (ref "R32") (pin "3") (pinfunction "TAP_3") (pintype "passive"))
    )
  )
)
